# PowCarbinBoard_Sensor.net
KiCad netlist of a schematic drawn in Altium Designer
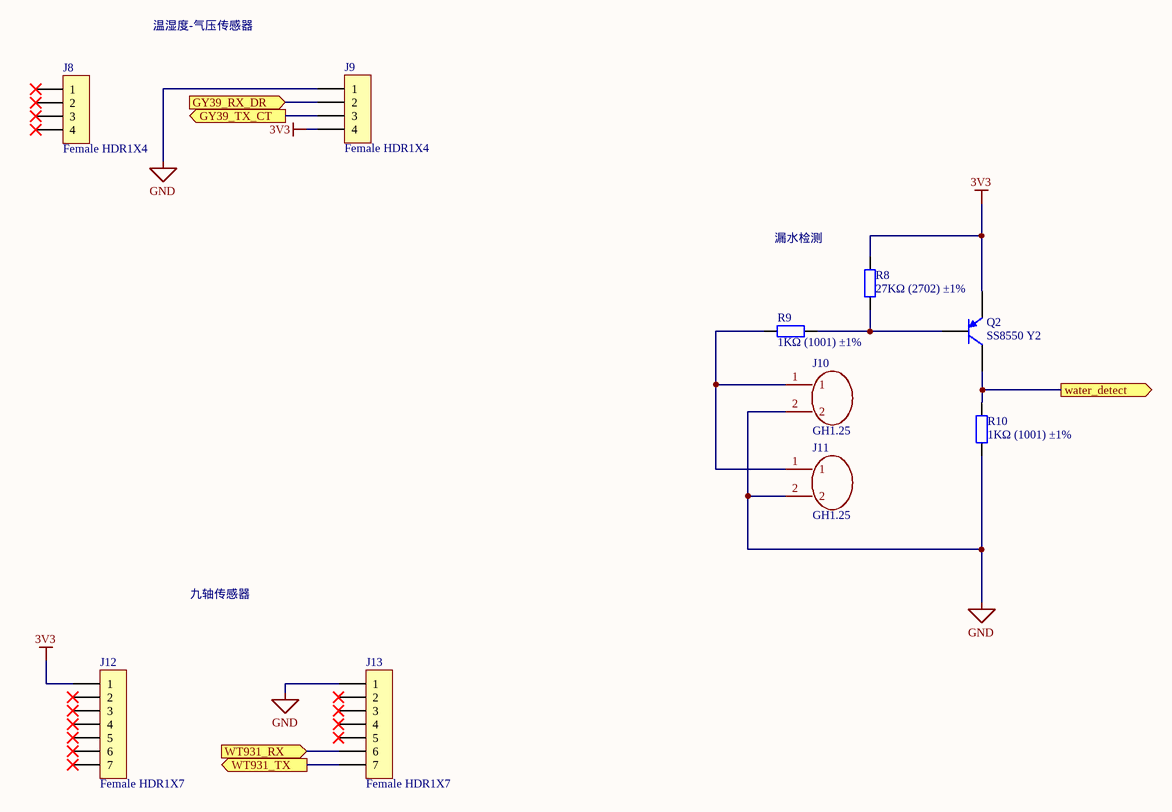
[diagram p0: PowCarbinBoard_Sensor.SchDoc]

(export (version "E")
  (design (tool "Eeschema 10.0.6"))
  (components
    (comp (ref "J8")
      (value "Female HDR1X4")
      (footprint "Fe-HDR1X4/2.54-S")
      (libsource (lib "排母") (part "Female HDR1X4"))
    )
    (comp (ref "J9")
      (value "Female HDR1X4")
      (footprint "Fe-HDR1X4/2.54-S")
      (libsource (lib "排母") (part "Female HDR1X4"))
    )
    (comp (ref "J10")
      (value "GH1.25")
      (footprint "GH1.25 2pin")
      (libsource (lib "MySchLib") (part "GH1.25 2pin"))
    )
    (comp (ref "J11")
      (value "GH1.25")
      (footprint "GH1.25 2pin")
      (libsource (lib "MySchLib") (part "GH1.25 2pin"))
    )
    (comp (ref "J12")
      (value "Female HDR1X7")
      (footprint "Fe-HDR1X7/2.54-S")
      (libsource (lib "排母") (part "Female HDR1X7"))
    )
    (comp (ref "J13")
      (value "Female HDR1X7")
      (footprint "Fe-HDR1X7/2.54-S")
      (libsource (lib "排母") (part "Female HDR1X7"))
    )
    (comp (ref "Q2")
      (value "SS8550 Y2")
      (footprint "SOT-23(SOT-23-3)")
      (description "三极管")
      (libsource (lib "Miscellaneous Devices LC") (part "SOT-23 SS8550 Y2"))
    )
    (comp (ref "R8")
      (value "27KΩ (2702) ±1%")
      (footprint "0603_R")
      (description "贴片电阻")
      (libsource (lib "Miscellaneous Devices LC") (part "0603 27KΩ (2702) 1%"))
    )
    (comp (ref "R9")
      (value "1KΩ (1001) ±1%")
      (footprint "0603_R")
      (description "贴片电阻")
      (libsource (lib "Miscellaneous Devices LC") (part "0603 1KΩ (1001) 1%"))
    )
    (comp (ref "R10")
      (value "1KΩ (1001) ±1%")
      (footprint "0603_R")
      (description "贴片电阻")
      (libsource (lib "") (part "0603 1KΩ (1001) 1%_1"))
    )
  )
  (nets
    (net (code "1") (name "/GY39_RX_DR") (class "Default")
      (node (ref "J9") (pin "2") (pinfunction "2_2") (pintype "passive"))
    )
    (net (code "2") (name "/GY39_TX_CT") (class "Default")
      (node (ref "J9") (pin "3") (pinfunction "3_3") (pintype "passive"))
    )
    (net (code "3") (name "/WT931_RX") (class "Default")
      (node (ref "J13") (pin "6") (pinfunction "6_6") (pintype "passive"))
    )
    (net (code "4") (name "/WT931_TX") (class "Default")
      (node (ref "J13") (pin "7") (pinfunction "7_7") (pintype "passive"))
    )
    (net (code "5") (name "/water_detect") (class "Default")
      (node (ref "Q2") (pin "3") (pinfunction "C_3") (pintype "passive"))
      (node (ref "R10") (pin "2") (pinfunction "2_2") (pintype "passive"))
    )
    (net (code "6") (name "3V3") (class "Default")
      (node (ref "J12") (pin "1") (pinfunction "1_1") (pintype "passive"))
      (node (ref "J9") (pin "4") (pinfunction "4_4") (pintype "passive"))
      (node (ref "Q2") (pin "2") (pinfunction "E_2") (pintype "passive"))
      (node (ref "R8") (pin "2") (pinfunction "2_2") (pintype "passive"))
    )
    (net (code "7") (name "GND") (class "Default")
      (node (ref "J10") (pin "2") (pinfunction "2_2") (pintype "passive"))
      (node (ref "J11") (pin "2") (pinfunction "2_2") (pintype "passive"))
      (node (ref "J13") (pin "1") (pinfunction "1_1") (pintype "passive"))
      (node (ref "J9") (pin "1") (pinfunction "1_1") (pintype "passive"))
      (node (ref "R10") (pin "1") (pinfunction "1_1") (pintype "passive"))
    )
    (net (code "8") (name "Net-(J10-Pad1)") (class "Default")
      (node (ref "J10") (pin "1") (pinfunction "1_1") (pintype "passive"))
      (node (ref "J11") (pin "1") (pinfunction "1_1") (pintype "passive"))
      (node (ref "R9") (pin "1") (pinfunction "1_1") (pintype "passive"))
    )
    (net (code "9") (name "Net-(Q2-B)") (class "Default")
      (node (ref "Q2") (pin "1") (pinfunction "B_1") (pintype "passive"))
      (node (ref "R8") (pin "1") (pinfunction "1_1") (pintype "passive"))
      (node (ref "R9") (pin "2") (pinfunction "2_2") (pintype "passive"))
    )
    (net (code "10") (name "unconnected-(J8-Pad1)") (class "Default")
      (node (ref "J8") (pin "1") (pinfunction "1_1") (pintype "passive+no_connect"))
    )
    (net (code "11") (name "unconnected-(J8-Pad2)") (class "Default")
      (node (ref "J8") (pin "2") (pinfunction "2_2") (pintype "passive+no_connect"))
    )
    (net (code "12") (name "unconnected-(J8-Pad3)") (class "Default")
      (node (ref "J8") (pin "3") (pinfunction "3_3") (pintype "passive+no_connect"))
    )
    (net (code "13") (name "unconnected-(J8-Pad4)") (class "Default")
      (node (ref "J8") (pin "4") (pinfunction "4_4") (pintype "passive+no_connect"))
    )
    (net (code "14") (name "unconnected-(J12-Pad2)") (class "Default")
      (node (ref "J12") (pin "2") (pinfunction "2_2") (pintype "passive+no_connect"))
    )
    (net (code "15") (name "unconnected-(J12-Pad3)") (class "Default")
      (node (ref "J12") (pin "3") (pinfunction "3_3") (pintype "passive+no_connect"))
    )
    (net (code "16") (name "unconnected-(J12-Pad4)") (class "Default")
      (node (ref "J12") (pin "4") (pinfunction "4_4") (pintype "passive+no_connect"))
    )
    (net (code "17") (name "unconnected-(J12-Pad5)") (class "Default")
      (node (ref "J12") (pin "5") (pinfunction "5_5") (pintype "passive+no_connect"))
    )
    (net (code "18") (name "unconnected-(J12-Pad6)") (class "Default")
      (node (ref "J12") (pin "6") (pinfunction "6_6") (pintype "passive+no_connect"))
    )
    (net (code "19") (name "unconnected-(J12-Pad7)") (class "Default")
      (node (ref "J12") (pin "7") (pinfunction "7_7") (pintype "passive+no_connect"))
    )
    (net (code "20") (name "unconnected-(J13-Pad2)") (class "Default")
      (node (ref "J13") (pin "2") (pinfunction "2_2") (pintype "passive+no_connect"))
    )
    (net (code "21") (name "unconnected-(J13-Pad3)") (class "Default")
      (node (ref "J13") (pin "3") (pinfunction "3_3") (pintype "passive+no_connect"))
    )
    (net (code "22") (name "unconnected-(J13-Pad4)") (class "Default")
      (node (ref "J13") (pin "4") (pinfunction "4_4") (pintype "passive+no_connect"))
    )
    (net (code "23") (name "unconnected-(J13-Pad5)") (class "Default")
      (node (ref "J13") (pin "5") (pinfunction "5_5") (pintype "passive+no_connect"))
    )
  )
)
